# Prototipo_2X_DobleCapa.net
KiCad netlist of a schematic drawn in EAGLE
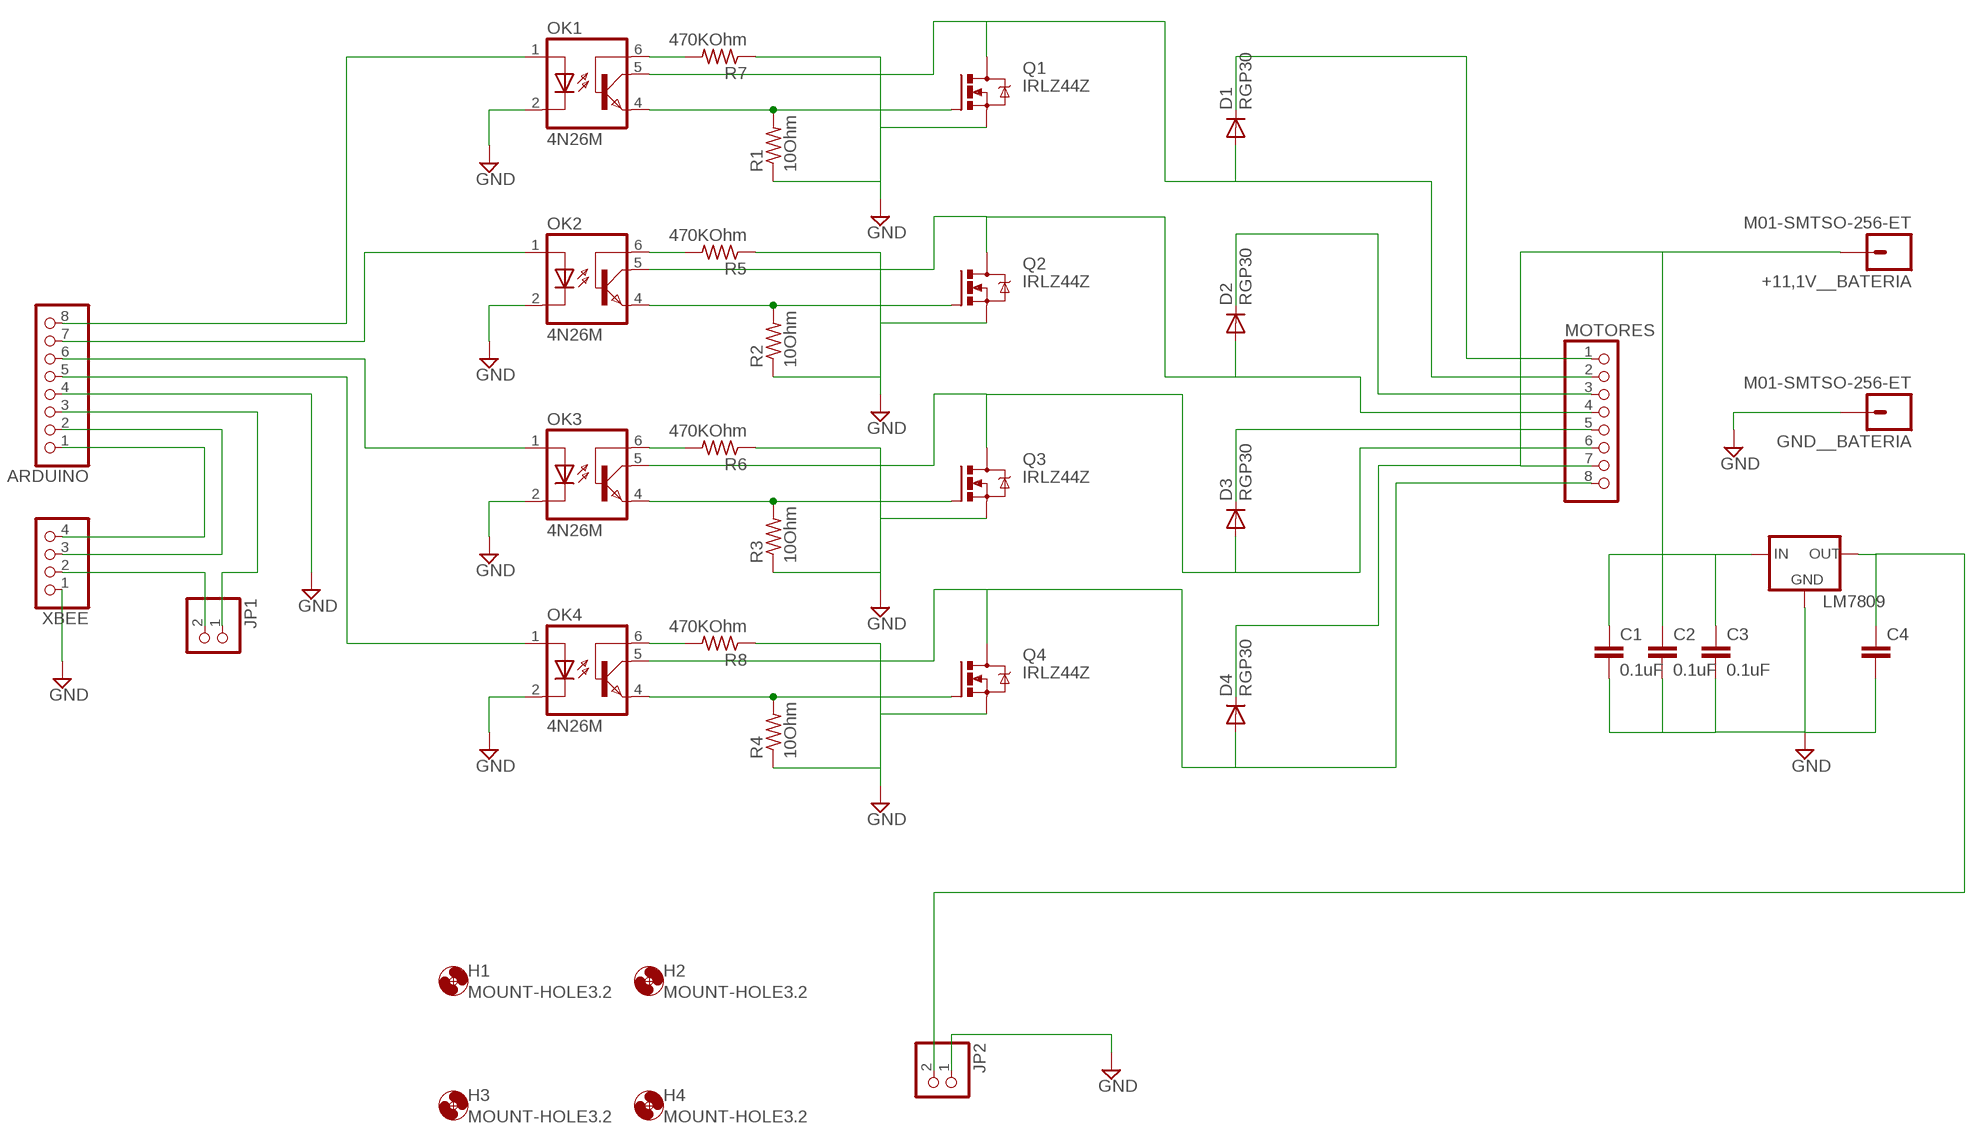
[diagram p0: schematic, sheet 1]

(export (version "E")
  (design (tool "Eeschema 10.0.6"))
  (components
    (comp (ref "+11,1V__BATERIA")
      (value "M01-SMTSO-256-ET")
      (footprint "eagle-import:SMTSO-256-ET")
      (libsource (lib "eagle-import") (part "M01-SMTSO-256-ET"))
    )
    (comp (ref "ARDUINO")
      (value "PINHD-1X8/90")
      (footprint "eagle-import:1X08_90")
      (libsource (lib "eagle-import") (part "PINHD-1X8/90"))
    )
    (comp (ref "C1")
      (value "0.1uF")
      (footprint "eagle-import:CAP-PTH-SMALL-KIT")
      (fields (field (name "PROD_ID") "CAP-08370"))
      (libsource (lib "eagle-import") (part "0.1UF-50V-20%(PTH)KIT-EZ"))
    )
    (comp (ref "C2")
      (value "0.1uF")
      (footprint "eagle-import:CAP-PTH-SMALL-KIT")
      (fields (field (name "PROD_ID") "CAP-08370"))
      (libsource (lib "eagle-import") (part "0.1UF-50V-20%(PTH)KIT-EZ"))
    )
    (comp (ref "C3")
      (value "0.1uF")
      (footprint "eagle-import:CAP-PTH-SMALL-KIT")
      (libsource (lib "eagle-import") (part "0.1UF-50V-20%(PTH)KIT-EZ"))
    )
    (comp (ref "C4")
      (value "0.1UF-50V-20%(PTH)KIT-EZ")
      (footprint "eagle-import:CAP-PTH-SMALL-KIT")
      (fields (field (name "PROD_ID") "CAP-08370"))
      (libsource (lib "eagle-import") (part "0.1UF-50V-20%(PTH)KIT-EZ"))
    )
    (comp (ref "D1")
      (value "RGP30")
      (footprint "eagle-import:DO201-15")
      (libsource (lib "eagle-import") (part "RGP30"))
    )
    (comp (ref "D2")
      (value "RGP30")
      (footprint "eagle-import:DO201-15")
      (libsource (lib "eagle-import") (part "RGP30"))
    )
    (comp (ref "D3")
      (value "RGP30")
      (footprint "eagle-import:DO201-15")
      (libsource (lib "eagle-import") (part "RGP30"))
    )
    (comp (ref "D4")
      (value "RGP30")
      (footprint "eagle-import:DO201-15")
      (libsource (lib "eagle-import") (part "RGP30"))
    )
    (comp (ref "GND__BATERIA")
      (value "M01-SMTSO-256-ET")
      (footprint "eagle-import:SMTSO-256-ET")
      (libsource (lib "eagle-import") (part "M01-SMTSO-256-ET"))
    )
    (comp (ref "H1")
      (value "MOUNT-HOLE3.2")
      (footprint "eagle-import:3,2")
      (libsource (lib "eagle-import") (part "MOUNT-HOLE3.2"))
    )
    (comp (ref "H2")
      (value "MOUNT-HOLE3.2")
      (footprint "eagle-import:3,2")
      (libsource (lib "eagle-import") (part "MOUNT-HOLE3.2"))
    )
    (comp (ref "H3")
      (value "MOUNT-HOLE3.2")
      (footprint "eagle-import:3,2")
      (libsource (lib "eagle-import") (part "MOUNT-HOLE3.2"))
    )
    (comp (ref "H4")
      (value "MOUNT-HOLE3.2")
      (footprint "eagle-import:3,2")
      (libsource (lib "eagle-import") (part "MOUNT-HOLE3.2"))
    )
    (comp (ref "JP1")
      (value "PINHD-1X2")
      (footprint "eagle-import:1X02")
      (libsource (lib "eagle-import") (part "PINHD-1X2"))
    )
    (comp (ref "JP2")
      (value "PINHD-1X2/90")
      (footprint "eagle-import:1X02_90")
      (libsource (lib "eagle-import") (part "PINHD-1X2/90"))
    )
    (comp (ref "LM7809")
      (value "78XXL")
      (footprint "eagle-import:78XXL")
      (libsource (lib "eagle-import") (part "78XXL"))
    )
    (comp (ref "MOTORES")
      (value "PINHD-1X8/90")
      (footprint "eagle-import:1X08_90")
      (libsource (lib "eagle-import") (part "PINHD-1X8/90"))
    )
    (comp (ref "OK1")
      (value "4N26M")
      (footprint "eagle-import:DIL06")
      (fields (field (name "MPN") "4N26-M"))
      (libsource (lib "eagle-import") (part "4N?M26"))
    )
    (comp (ref "OK2")
      (value "4N26M")
      (footprint "eagle-import:DIL06")
      (fields (field (name "MPN") "4N26-M"))
      (libsource (lib "eagle-import") (part "4N?M26"))
    )
    (comp (ref "OK3")
      (value "4N26M")
      (footprint "eagle-import:DIL06")
      (fields (field (name "MPN") "4N26-M"))
      (libsource (lib "eagle-import") (part "4N?M26"))
    )
    (comp (ref "OK4")
      (value "4N26M")
      (footprint "eagle-import:DIL06")
      (fields (field (name "MPN") "4N26-M"))
      (libsource (lib "eagle-import") (part "4N?M26"))
    )
    (comp (ref "Q1")
      (value "IRLZ44Z")
      (footprint "eagle-import:TO220BH")
      (libsource (lib "eagle-import") (part "IRLZ44Z"))
    )
    (comp (ref "Q2")
      (value "IRLZ44Z")
      (footprint "eagle-import:TO220BH")
      (libsource (lib "eagle-import") (part "IRLZ44Z"))
    )
    (comp (ref "Q3")
      (value "IRLZ44Z")
      (footprint "eagle-import:TO220BH")
      (libsource (lib "eagle-import") (part "IRLZ44Z"))
    )
    (comp (ref "Q4")
      (value "IRLZ44Z")
      (footprint "eagle-import:TO220BH")
      (libsource (lib "eagle-import") (part "IRLZ44Z"))
    )
    (comp (ref "R1")
      (value "10Ohm")
      (footprint "eagle-import:0207_7")
      (libsource (lib "eagle-import") (part "R-US_0207/7"))
    )
    (comp (ref "R2")
      (value "10Ohm")
      (footprint "eagle-import:0207_7")
      (libsource (lib "eagle-import") (part "R-US_0207/7"))
    )
    (comp (ref "R3")
      (value "10Ohm")
      (footprint "eagle-import:0207_7")
      (libsource (lib "eagle-import") (part "R-US_0207/7"))
    )
    (comp (ref "R4")
      (value "10Ohm")
      (footprint "eagle-import:0207_7")
      (libsource (lib "eagle-import") (part "R-US_0207/7"))
    )
    (comp (ref "R5")
      (value "470KOhm")
      (footprint "eagle-import:0207_7")
      (libsource (lib "eagle-import") (part "resistor_R-US_0207/7"))
    )
    (comp (ref "R6")
      (value "470KOhm")
      (footprint "eagle-import:0207_7")
      (libsource (lib "eagle-import") (part "resistor_R-US_0207/7"))
    )
    (comp (ref "R7")
      (value "470KOhm")
      (footprint "eagle-import:0207_7")
      (libsource (lib "eagle-import") (part "resistor_R-US_0207/7"))
    )
    (comp (ref "R8")
      (value "470KOhm")
      (footprint "eagle-import:0207_7")
      (libsource (lib "eagle-import") (part "resistor_R-US_0207/7"))
    )
    (comp (ref "XBEE")
      (value "PINHD-1X4")
      (footprint "eagle-import:1X04")
      (libsource (lib "eagle-import") (part "PINHD-1X4"))
    )
  )
  (nets
    (net (code "1") (name "GND") (class "Default")
      (node (ref "ARDUINO") (pin "4") (pinfunction "4_4") (pintype "passive"))
      (node (ref "C1") (pin "2") (pinfunction "2_2") (pintype "passive"))
      (node (ref "C2") (pin "2") (pinfunction "2_2") (pintype "passive"))
      (node (ref "C3") (pin "2") (pinfunction "2_2") (pintype "passive"))
      (node (ref "C4") (pin "2") (pinfunction "2_2") (pintype "passive"))
      (node (ref "GND__BATERIA") (pin "P$1") (pinfunction "1_P$1") (pintype "passive"))
      (node (ref "JP2") (pin "1") (pinfunction "1_1") (pintype "passive"))
      (node (ref "LM7809") (pin "GND") (pinfunction "GND_GND") (pintype "input"))
      (node (ref "OK1") (pin "2") (pinfunction "C_2") (pintype "passive"))
      (node (ref "OK2") (pin "2") (pinfunction "C_2") (pintype "passive"))
      (node (ref "OK3") (pin "2") (pinfunction "C_2") (pintype "passive"))
      (node (ref "OK4") (pin "2") (pinfunction "C_2") (pintype "passive"))
      (node (ref "Q1") (pin "S") (pinfunction "S_S") (pintype "passive"))
      (node (ref "Q2") (pin "S") (pinfunction "S_S") (pintype "passive"))
      (node (ref "Q3") (pin "S") (pinfunction "S_S") (pintype "passive"))
      (node (ref "Q4") (pin "S") (pinfunction "S_S") (pintype "passive"))
      (node (ref "R1") (pin "1") (pinfunction "1_1") (pintype "passive"))
      (node (ref "R2") (pin "1") (pinfunction "1_1") (pintype "passive"))
      (node (ref "R3") (pin "1") (pinfunction "1_1") (pintype "passive"))
      (node (ref "R4") (pin "1") (pinfunction "1_1") (pintype "passive"))
      (node (ref "R5") (pin "1") (pinfunction "1_1") (pintype "passive"))
      (node (ref "R6") (pin "1") (pinfunction "1_1") (pintype "passive"))
      (node (ref "R7") (pin "1") (pinfunction "1_1") (pintype "passive"))
      (node (ref "R8") (pin "1") (pinfunction "1_1") (pintype "passive"))
      (node (ref "XBEE") (pin "1") (pinfunction "1_1") (pintype "passive"))
    )
    (net (code "2") (name "Net-(+11,1V__BATERIA-1)") (class "Default")
      (node (ref "+11,1V__BATERIA") (pin "P$1") (pinfunction "1_P$1") (pintype "passive"))
      (node (ref "C1") (pin "1") (pinfunction "1_1") (pintype "passive"))
      (node (ref "C2") (pin "1") (pinfunction "1_1") (pintype "passive"))
      (node (ref "C3") (pin "1") (pinfunction "1_1") (pintype "passive"))
      (node (ref "D1") (pin "C") (pinfunction "C_C") (pintype "passive"))
      (node (ref "D2") (pin "C") (pinfunction "C_C") (pintype "passive"))
      (node (ref "D3") (pin "C") (pinfunction "C_C") (pintype "passive"))
      (node (ref "D4") (pin "C") (pinfunction "C_C") (pintype "passive"))
      (node (ref "LM7809") (pin "IN") (pinfunction "IN_IN") (pintype "input"))
      (node (ref "MOTORES") (pin "1") (pinfunction "1_1") (pintype "passive"))
      (node (ref "MOTORES") (pin "3") (pinfunction "3_3") (pintype "passive"))
      (node (ref "MOTORES") (pin "5") (pinfunction "5_5") (pintype "passive"))
      (node (ref "MOTORES") (pin "7") (pinfunction "7_7") (pintype "passive"))
    )
    (net (code "3") (name "Net-(ARDUINO-Pad1)") (class "Default")
      (node (ref "ARDUINO") (pin "1") (pinfunction "1_1") (pintype "passive"))
      (node (ref "XBEE") (pin "4") (pinfunction "4_4") (pintype "passive"))
    )
    (net (code "4") (name "Net-(ARDUINO-Pad2)") (class "Default")
      (node (ref "ARDUINO") (pin "2") (pinfunction "2_2") (pintype "passive"))
      (node (ref "XBEE") (pin "3") (pinfunction "3_3") (pintype "passive"))
    )
    (net (code "5") (name "Net-(ARDUINO-Pad3)") (class "Default")
      (node (ref "ARDUINO") (pin "3") (pinfunction "3_3") (pintype "passive"))
      (node (ref "JP1") (pin "1") (pinfunction "1_1") (pintype "passive"))
    )
    (net (code "6") (name "Net-(C4-Pad1)") (class "Default")
      (node (ref "C4") (pin "1") (pinfunction "1_1") (pintype "passive"))
      (node (ref "JP2") (pin "2") (pinfunction "2_2") (pintype "passive"))
      (node (ref "LM7809") (pin "OUT") (pinfunction "OUT_OUT") (pintype "passive"))
    )
    (net (code "7") (name "Net-(JP1-Pad2)") (class "Default")
      (node (ref "JP1") (pin "2") (pinfunction "2_2") (pintype "passive"))
      (node (ref "XBEE") (pin "2") (pinfunction "2_2") (pintype "passive"))
    )
    (net (code "8") (name "Net-(OK1-A)") (class "Default")
      (node (ref "ARDUINO") (pin "8") (pinfunction "8_8") (pintype "passive"))
      (node (ref "OK1") (pin "1") (pinfunction "A_1") (pintype "passive"))
    )
    (net (code "9") (name "Net-(OK1-BAS)") (class "Default")
      (node (ref "OK1") (pin "6") (pinfunction "BAS_6") (pintype "passive"))
      (node (ref "R7") (pin "2") (pinfunction "2_2") (pintype "passive"))
    )
    (net (code "10") (name "Net-(OK1-COL)") (class "Default")
      (node (ref "D1") (pin "A") (pinfunction "A_A") (pintype "passive"))
      (node (ref "MOTORES") (pin "2") (pinfunction "2_2") (pintype "passive"))
      (node (ref "OK1") (pin "5") (pinfunction "COL_5") (pintype "passive"))
      (node (ref "Q1") (pin "D") (pinfunction "D_D") (pintype "passive"))
    )
    (net (code "11") (name "Net-(OK1-EMI)") (class "Default")
      (node (ref "OK1") (pin "4") (pinfunction "EMI_4") (pintype "passive"))
      (node (ref "Q1") (pin "G") (pinfunction "G_G") (pintype "passive"))
      (node (ref "R1") (pin "2") (pinfunction "2_2") (pintype "passive"))
    )
    (net (code "12") (name "Net-(OK2-A)") (class "Default")
      (node (ref "ARDUINO") (pin "7") (pinfunction "7_7") (pintype "passive"))
      (node (ref "OK2") (pin "1") (pinfunction "A_1") (pintype "passive"))
    )
    (net (code "13") (name "Net-(OK2-BAS)") (class "Default")
      (node (ref "OK2") (pin "6") (pinfunction "BAS_6") (pintype "passive"))
      (node (ref "R5") (pin "2") (pinfunction "2_2") (pintype "passive"))
    )
    (net (code "14") (name "Net-(OK2-COL)") (class "Default")
      (node (ref "D2") (pin "A") (pinfunction "A_A") (pintype "passive"))
      (node (ref "MOTORES") (pin "4") (pinfunction "4_4") (pintype "passive"))
      (node (ref "OK2") (pin "5") (pinfunction "COL_5") (pintype "passive"))
      (node (ref "Q2") (pin "D") (pinfunction "D_D") (pintype "passive"))
    )
    (net (code "15") (name "Net-(OK2-EMI)") (class "Default")
      (node (ref "OK2") (pin "4") (pinfunction "EMI_4") (pintype "passive"))
      (node (ref "Q2") (pin "G") (pinfunction "G_G") (pintype "passive"))
      (node (ref "R2") (pin "2") (pinfunction "2_2") (pintype "passive"))
    )
    (net (code "16") (name "Net-(OK3-A)") (class "Default")
      (node (ref "ARDUINO") (pin "6") (pinfunction "6_6") (pintype "passive"))
      (node (ref "OK3") (pin "1") (pinfunction "A_1") (pintype "passive"))
    )
    (net (code "17") (name "Net-(OK3-BAS)") (class "Default")
      (node (ref "OK3") (pin "6") (pinfunction "BAS_6") (pintype "passive"))
      (node (ref "R6") (pin "2") (pinfunction "2_2") (pintype "passive"))
    )
    (net (code "18") (name "Net-(OK3-COL)") (class "Default")
      (node (ref "D3") (pin "A") (pinfunction "A_A") (pintype "passive"))
      (node (ref "MOTORES") (pin "6") (pinfunction "6_6") (pintype "passive"))
      (node (ref "OK3") (pin "5") (pinfunction "COL_5") (pintype "passive"))
      (node (ref "Q3") (pin "D") (pinfunction "D_D") (pintype "passive"))
    )
    (net (code "19") (name "Net-(OK3-EMI)") (class "Default")
      (node (ref "OK3") (pin "4") (pinfunction "EMI_4") (pintype "passive"))
      (node (ref "Q3") (pin "G") (pinfunction "G_G") (pintype "passive"))
      (node (ref "R3") (pin "2") (pinfunction "2_2") (pintype "passive"))
    )
    (net (code "20") (name "Net-(OK4-A)") (class "Default")
      (node (ref "ARDUINO") (pin "5") (pinfunction "5_5") (pintype "passive"))
      (node (ref "OK4") (pin "1") (pinfunction "A_1") (pintype "passive"))
    )
    (net (code "21") (name "Net-(OK4-BAS)") (class "Default")
      (node (ref "OK4") (pin "6") (pinfunction "BAS_6") (pintype "passive"))
      (node (ref "R8") (pin "2") (pinfunction "2_2") (pintype "passive"))
    )
    (net (code "22") (name "Net-(OK4-COL)") (class "Default")
      (node (ref "D4") (pin "A") (pinfunction "A_A") (pintype "passive"))
      (node (ref "MOTORES") (pin "8") (pinfunction "8_8") (pintype "passive"))
      (node (ref "OK4") (pin "5") (pinfunction "COL_5") (pintype "passive"))
      (node (ref "Q4") (pin "D") (pinfunction "D_D") (pintype "passive"))
    )
    (net (code "23") (name "Net-(OK4-EMI)") (class "Default")
      (node (ref "OK4") (pin "4") (pinfunction "EMI_4") (pintype "passive"))
      (node (ref "Q4") (pin "G") (pinfunction "G_G") (pintype "passive"))
      (node (ref "R4") (pin "2") (pinfunction "2_2") (pintype "passive"))
    )
  )
)
